# crosstalk-2.net
KiCad netlist of a schematic drawn in Altium Designer
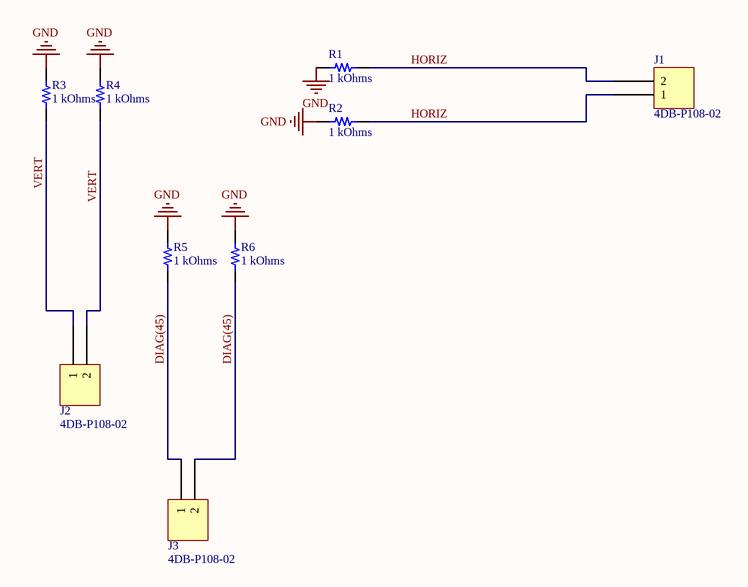
[diagram p0: crosstalk-2.SchDoc]

(export (version "E")
  (design (tool "Eeschema 10.0.6"))
  (components
    (comp (ref "J1")
      (value "4DB-P108-02")
      (footprint "TE 4DB-P108-02")
      (description "CONN BARRIER STRIP 2CIRC 0.325\"")
      (fields (field (name "MANUFACTURER") "TE Connectivity AMP Connectors"))
      (libsource (lib "") (part "2 Pin_1"))
    )
    (comp (ref "J2")
      (value "4DB-P108-02")
      (footprint "TE 4DB-P108-02")
      (description "CONN BARRIER STRIP 2CIRC 0.325\"")
      (fields (field (name "MANUFACTURER") "TE Connectivity AMP Connectors"))
      (libsource (lib "Celestial Altium Library - altium_library") (part "2 Pin"))
    )
    (comp (ref "J3")
      (value "4DB-P108-02")
      (footprint "TE 4DB-P108-02")
      (description "CONN BARRIER STRIP 2CIRC 0.325\"")
      (fields (field (name "MANUFACTURER") "TE Connectivity AMP Connectors"))
      (libsource (lib "Celestial Altium Library - altium_library") (part "2 Pin"))
    )
    (comp (ref "R1")
      (value "1 kOhms")
      (footprint "RES 0603_1608")
      (description "RES SMD 1K OHM 0.1% 1/16W 0603")
      (fields
        (field (name "PART NUMBER") "CPF0603B1K0E")
        (field (name "MANUFACTURER") "TE Connectivity Passive Product")
      )
      (libsource (lib "Celestial Altium Library - altium_library") (part "Resistor"))
    )
    (comp (ref "R2")
      (value "1 kOhms")
      (footprint "RES 0603_1608")
      (description "RES SMD 1K OHM 0.1% 1/16W 0603")
      (fields
        (field (name "PART NUMBER") "CPF0603B1K0E")
        (field (name "MANUFACTURER") "TE Connectivity Passive Product")
      )
      (libsource (lib "Celestial Altium Library - altium_library") (part "Resistor"))
    )
    (comp (ref "R3")
      (value "1 kOhms")
      (footprint "RES 0603_1608")
      (description "RES SMD 1K OHM 0.1% 1/16W 0603")
      (fields
        (field (name "PART NUMBER") "CPF0603B1K0E")
        (field (name "MANUFACTURER") "TE Connectivity Passive Product")
      )
      (libsource (lib "Celestial Altium Library - altium_library") (part "Resistor"))
    )
    (comp (ref "R4")
      (value "1 kOhms")
      (footprint "RES 0603_1608")
      (description "RES SMD 1K OHM 0.1% 1/16W 0603")
      (fields
        (field (name "PART NUMBER") "CPF0603B1K0E")
        (field (name "MANUFACTURER") "TE Connectivity Passive Product")
      )
      (libsource (lib "Celestial Altium Library - altium_library") (part "Resistor"))
    )
    (comp (ref "R5")
      (value "1 kOhms")
      (footprint "RES 0603_1608")
      (description "RES SMD 1K OHM 0.1% 1/16W 0603")
      (fields
        (field (name "PART NUMBER") "CPF0603B1K0E")
        (field (name "MANUFACTURER") "TE Connectivity Passive Product")
      )
      (libsource (lib "Celestial Altium Library - altium_library") (part "Resistor"))
    )
    (comp (ref "R6")
      (value "1 kOhms")
      (footprint "RES 0603_1608")
      (description "RES SMD 1K OHM 0.1% 1/16W 0603")
      (fields
        (field (name "PART NUMBER") "CPF0603B1K0E")
        (field (name "MANUFACTURER") "TE Connectivity Passive Product")
      )
      (libsource (lib "Celestial Altium Library - altium_library") (part "Resistor"))
    )
  )
  (nets
    (net (code "1") (name "/DIAG(45)") (class "Default")
      (node (ref "J3") (pin "1") (pinfunction "1_1") (pintype "passive"))
      (node (ref "J3") (pin "2") (pinfunction "2_2") (pintype "passive"))
      (node (ref "R5") (pin "2") (pinfunction "2_2") (pintype "passive"))
      (node (ref "R6") (pin "2") (pinfunction "2_2") (pintype "passive"))
    )
    (net (code "2") (name "/HORIZ") (class "Default")
      (node (ref "J1") (pin "1") (pinfunction "1_1") (pintype "passive"))
      (node (ref "J1") (pin "2") (pinfunction "2_2") (pintype "passive"))
      (node (ref "R1") (pin "1") (pinfunction "1_1") (pintype "passive"))
      (node (ref "R2") (pin "1") (pinfunction "1_1") (pintype "passive"))
    )
    (net (code "3") (name "/VERT") (class "Default")
      (node (ref "J2") (pin "1") (pinfunction "1_1") (pintype "passive"))
      (node (ref "J2") (pin "2") (pinfunction "2_2") (pintype "passive"))
      (node (ref "R3") (pin "1") (pinfunction "1_1") (pintype "passive"))
      (node (ref "R4") (pin "1") (pinfunction "1_1") (pintype "passive"))
    )
    (net (code "4") (name "GND") (class "Default")
      (node (ref "R1") (pin "2") (pinfunction "2_2") (pintype "passive"))
      (node (ref "R2") (pin "2") (pinfunction "2_2") (pintype "passive"))
      (node (ref "R3") (pin "2") (pinfunction "2_2") (pintype "passive"))
      (node (ref "R4") (pin "2") (pinfunction "2_2") (pintype "passive"))
      (node (ref "R5") (pin "1") (pinfunction "1_1") (pintype "passive"))
      (node (ref "R6") (pin "1") (pinfunction "1_1") (pintype "passive"))
    )
  )
)
